# ProPrj_Arduino_Project_2026-04-11.net
KiCad netlist of a schematic drawn in EasyEDA Pro
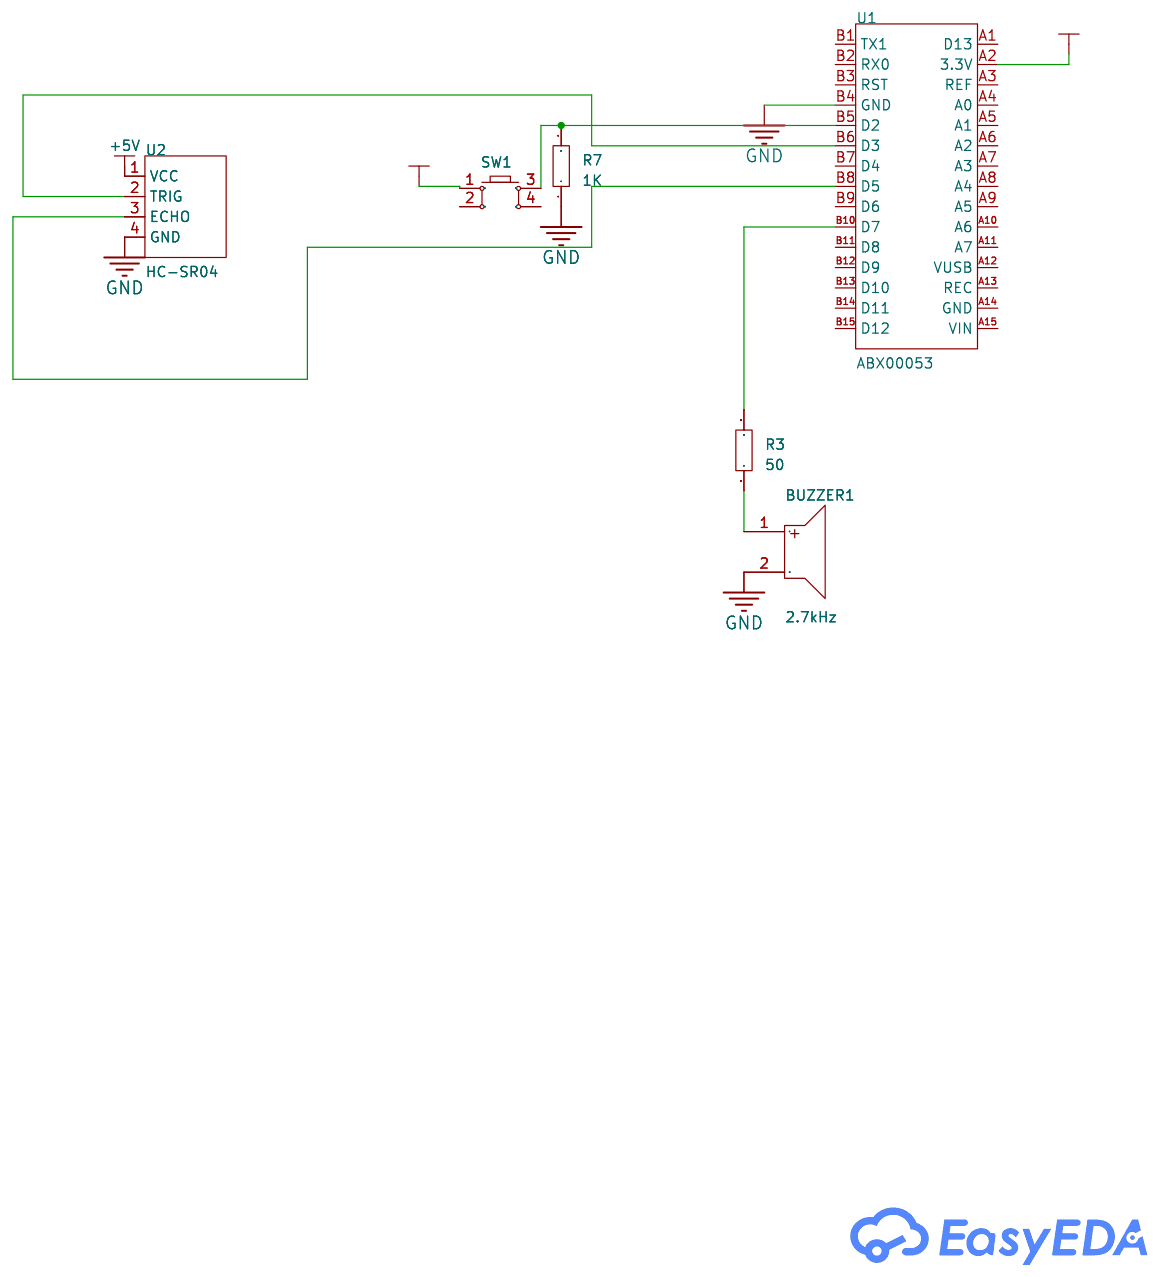
[diagram p0: schematic sheet]

(export (version "E")
  (design (tool "Eeschema 10.0.6"))
  (components
    (comp (ref "BUZZER1")
      (value "2.7kHz")
      (footprint "easyedapro:BUZ-TH_BD9.0-P4.00-D0.6-FD")
      (fields (field (name "Manufacturer Part") "QMB-09B-03") (field (name "Manufacturer") "华能"))
      (libsource (lib "easyedapro") (part "QMB-09B-03"))
    )
    (comp (ref "R3") (value "50") (footprint "easyedapro:R0603") (libsource (lib "easyedapro") (part "Res")))
    (comp (ref "R7") (value "1K") (footprint "easyedapro:R0603") (libsource (lib "easyedapro") (part "Res")))
    (comp (ref "SW1")
      (value "~")
      (footprint "easyedapro:SW-SMD_4P-L6.0-W6.0-P4.50-LS9.0-2")
      (libsource (lib "easyedapro") (part "轻触按键"))
    )
    (comp (ref "U1")
      (value "ABX00053")
      (footprint "easyedapro:COMM-TH_ABX00092")
      (fields (field (name "Manufacturer") "arduino"))
      (libsource (lib "easyedapro") (part "ABX00053"))
    )
    (comp (ref "U2")
      (value "HC-SR04")
      (footprint "easyedapro:TH_HC-SR04V")
      (fields (field (name "Manufacturer") "Universal Microelectronics"))
      (libsource (lib "easyedapro") (part "HC-SR04"))
    )
  )
  (nets
    (net (code "1") (name "+5V") (class "Default")
      (node (ref "U2") (pin "1") (pinfunction "VCC_1") (pintype "unspecified"))
    )
    (net (code "2") (name "3.3V") (class "Default")
      (node (ref "U1") (pin "A2") (pinfunction "3.3V_A2") (pintype "unspecified"))
    )
    (net (code "3") (name "5V") (class "Default")
      (node (ref "SW1") (pin "1") (pinfunction "1_1") (pintype "input"))
    )
    (net (code "4") (name "GND") (class "Default")
      (node (ref "BUZZER1") (pin "2") (pinfunction "2_2") (pintype "unspecified"))
      (node (ref "R7") (pin "1") (pinfunction "1_1") (pintype "input"))
      (node (ref "U1") (pin "B4") (pinfunction "GND_B4") (pintype "unspecified"))
      (node (ref "U2") (pin "4") (pinfunction "GND_4") (pintype "unspecified"))
    )
    (net (code "5") (name "Net-(BUZZER1-Pad1)") (class "Default")
      (node (ref "BUZZER1") (pin "1") (pinfunction "1_1") (pintype "unspecified"))
      (node (ref "R3") (pin "1") (pinfunction "1_1") (pintype "input"))
    )
    (net (code "6") (name "Net-(U1-D2)") (class "Default")
      (node (ref "R7") (pin "2") (pinfunction "2_2") (pintype "input"))
      (node (ref "SW1") (pin "3") (pinfunction "3_3") (pintype "input"))
      (node (ref "U1") (pin "B5") (pinfunction "D2_B5") (pintype "unspecified"))
    )
    (net (code "7") (name "Net-(U1-D3)") (class "Default")
      (node (ref "U1") (pin "B6") (pinfunction "D3_B6") (pintype "unspecified"))
      (node (ref "U2") (pin "2") (pinfunction "TRIG_2") (pintype "unspecified"))
    )
    (net (code "8") (name "Net-(U1-D5)") (class "Default")
      (node (ref "U1") (pin "B8") (pinfunction "D5_B8") (pintype "unspecified"))
      (node (ref "U2") (pin "3") (pinfunction "ECHO_3") (pintype "unspecified"))
    )
    (net (code "9") (name "Net-(U1-D7)") (class "Default")
      (node (ref "R3") (pin "2") (pinfunction "2_2") (pintype "input"))
      (node (ref "U1") (pin "B10") (pinfunction "D7_B10") (pintype "unspecified"))
    )
    (net (code "10") (name "unconnected-(SW1-Pad2)") (class "Default")
      (node (ref "SW1") (pin "2") (pinfunction "2_2") (pintype "input"))
    )
    (net (code "11") (name "unconnected-(SW1-Pad4)") (class "Default")
      (node (ref "SW1") (pin "4") (pinfunction "4_4") (pintype "input"))
    )
    (net (code "12") (name "unconnected-(U1-A0-PadA4)") (class "Default")
      (node (ref "U1") (pin "A4") (pinfunction "A0_A4") (pintype "unspecified"))
    )
    (net (code "13") (name "unconnected-(U1-A1-PadA5)") (class "Default")
      (node (ref "U1") (pin "A5") (pinfunction "A1_A5") (pintype "unspecified"))
    )
    (net (code "14") (name "unconnected-(U1-A2-PadA6)") (class "Default")
      (node (ref "U1") (pin "A6") (pinfunction "A2_A6") (pintype "unspecified"))
    )
    (net (code "15") (name "unconnected-(U1-A3-PadA7)") (class "Default")
      (node (ref "U1") (pin "A7") (pinfunction "A3_A7") (pintype "unspecified"))
    )
    (net (code "16") (name "unconnected-(U1-A4-PadA8)") (class "Default")
      (node (ref "U1") (pin "A8") (pinfunction "A4_A8") (pintype "unspecified"))
    )
    (net (code "17") (name "unconnected-(U1-A5-PadA9)") (class "Default")
      (node (ref "U1") (pin "A9") (pinfunction "A5_A9") (pintype "unspecified"))
    )
    (net (code "18") (name "unconnected-(U1-A6-PadA10)") (class "Default")
      (node (ref "U1") (pin "A10") (pinfunction "A6_A10") (pintype "unspecified"))
    )
    (net (code "19") (name "unconnected-(U1-A7-PadA11)") (class "Default")
      (node (ref "U1") (pin "A11") (pinfunction "A7_A11") (pintype "unspecified"))
    )
    (net (code "20") (name "unconnected-(U1-D4-PadB7)") (class "Default")
      (node (ref "U1") (pin "B7") (pinfunction "D4_B7") (pintype "unspecified"))
    )
    (net (code "21") (name "unconnected-(U1-D6-PadB9)") (class "Default")
      (node (ref "U1") (pin "B9") (pinfunction "D6_B9") (pintype "unspecified"))
    )
    (net (code "22") (name "unconnected-(U1-D8-PadB11)") (class "Default")
      (node (ref "U1") (pin "B11") (pinfunction "D8_B11") (pintype "unspecified"))
    )
    (net (code "23") (name "unconnected-(U1-D9-PadB12)") (class "Default")
      (node (ref "U1") (pin "B12") (pinfunction "D9_B12") (pintype "unspecified"))
    )
    (net (code "24") (name "unconnected-(U1-D10-PadB13)") (class "Default")
      (node (ref "U1") (pin "B13") (pinfunction "D10_B13") (pintype "unspecified"))
    )
    (net (code "25") (name "unconnected-(U1-D11-PadB14)") (class "Default")
      (node (ref "U1") (pin "B14") (pinfunction "D11_B14") (pintype "unspecified"))
    )
    (net (code "26") (name "unconnected-(U1-D12-PadB15)") (class "Default")
      (node (ref "U1") (pin "B15") (pinfunction "D12_B15") (pintype "unspecified"))
    )
    (net (code "27") (name "unconnected-(U1-D13-PadA1)") (class "Default")
      (node (ref "U1") (pin "A1") (pinfunction "D13_A1") (pintype "unspecified"))
    )
    (net (code "28") (name "unconnected-(U1-GND-PadA14)") (class "Default")
      (node (ref "U1") (pin "A14") (pinfunction "GND_A14") (pintype "unspecified"))
    )
    (net (code "29") (name "unconnected-(U1-REC-PadA13)") (class "Default")
      (node (ref "U1") (pin "A13") (pinfunction "REC_A13") (pintype "unspecified"))
    )
    (net (code "30") (name "unconnected-(U1-REF-PadA3)") (class "Default")
      (node (ref "U1") (pin "A3") (pinfunction "REF_A3") (pintype "unspecified"))
    )
    (net (code "31") (name "unconnected-(U1-RST-PadB3)") (class "Default")
      (node (ref "U1") (pin "B3") (pinfunction "RST_B3") (pintype "unspecified"))
    )
    (net (code "32") (name "unconnected-(U1-RX0-PadB2)") (class "Default")
      (node (ref "U1") (pin "B2") (pinfunction "RX0_B2") (pintype "unspecified"))
    )
    (net (code "33") (name "unconnected-(U1-TX1-PadB1)") (class "Default")
      (node (ref "U1") (pin "B1") (pinfunction "TX1_B1") (pintype "unspecified"))
    )
    (net (code "34") (name "unconnected-(U1-VIN-PadA15)") (class "Default")
      (node (ref "U1") (pin "A15") (pinfunction "VIN_A15") (pintype "unspecified"))
    )
    (net (code "35") (name "unconnected-(U1-VUSB-PadA12)") (class "Default")
      (node (ref "U1") (pin "A12") (pinfunction "VUSB_A12") (pintype "unspecified"))
    )
  )
)
